# TX.net
KiCad netlist of a schematic drawn in Altium Designer
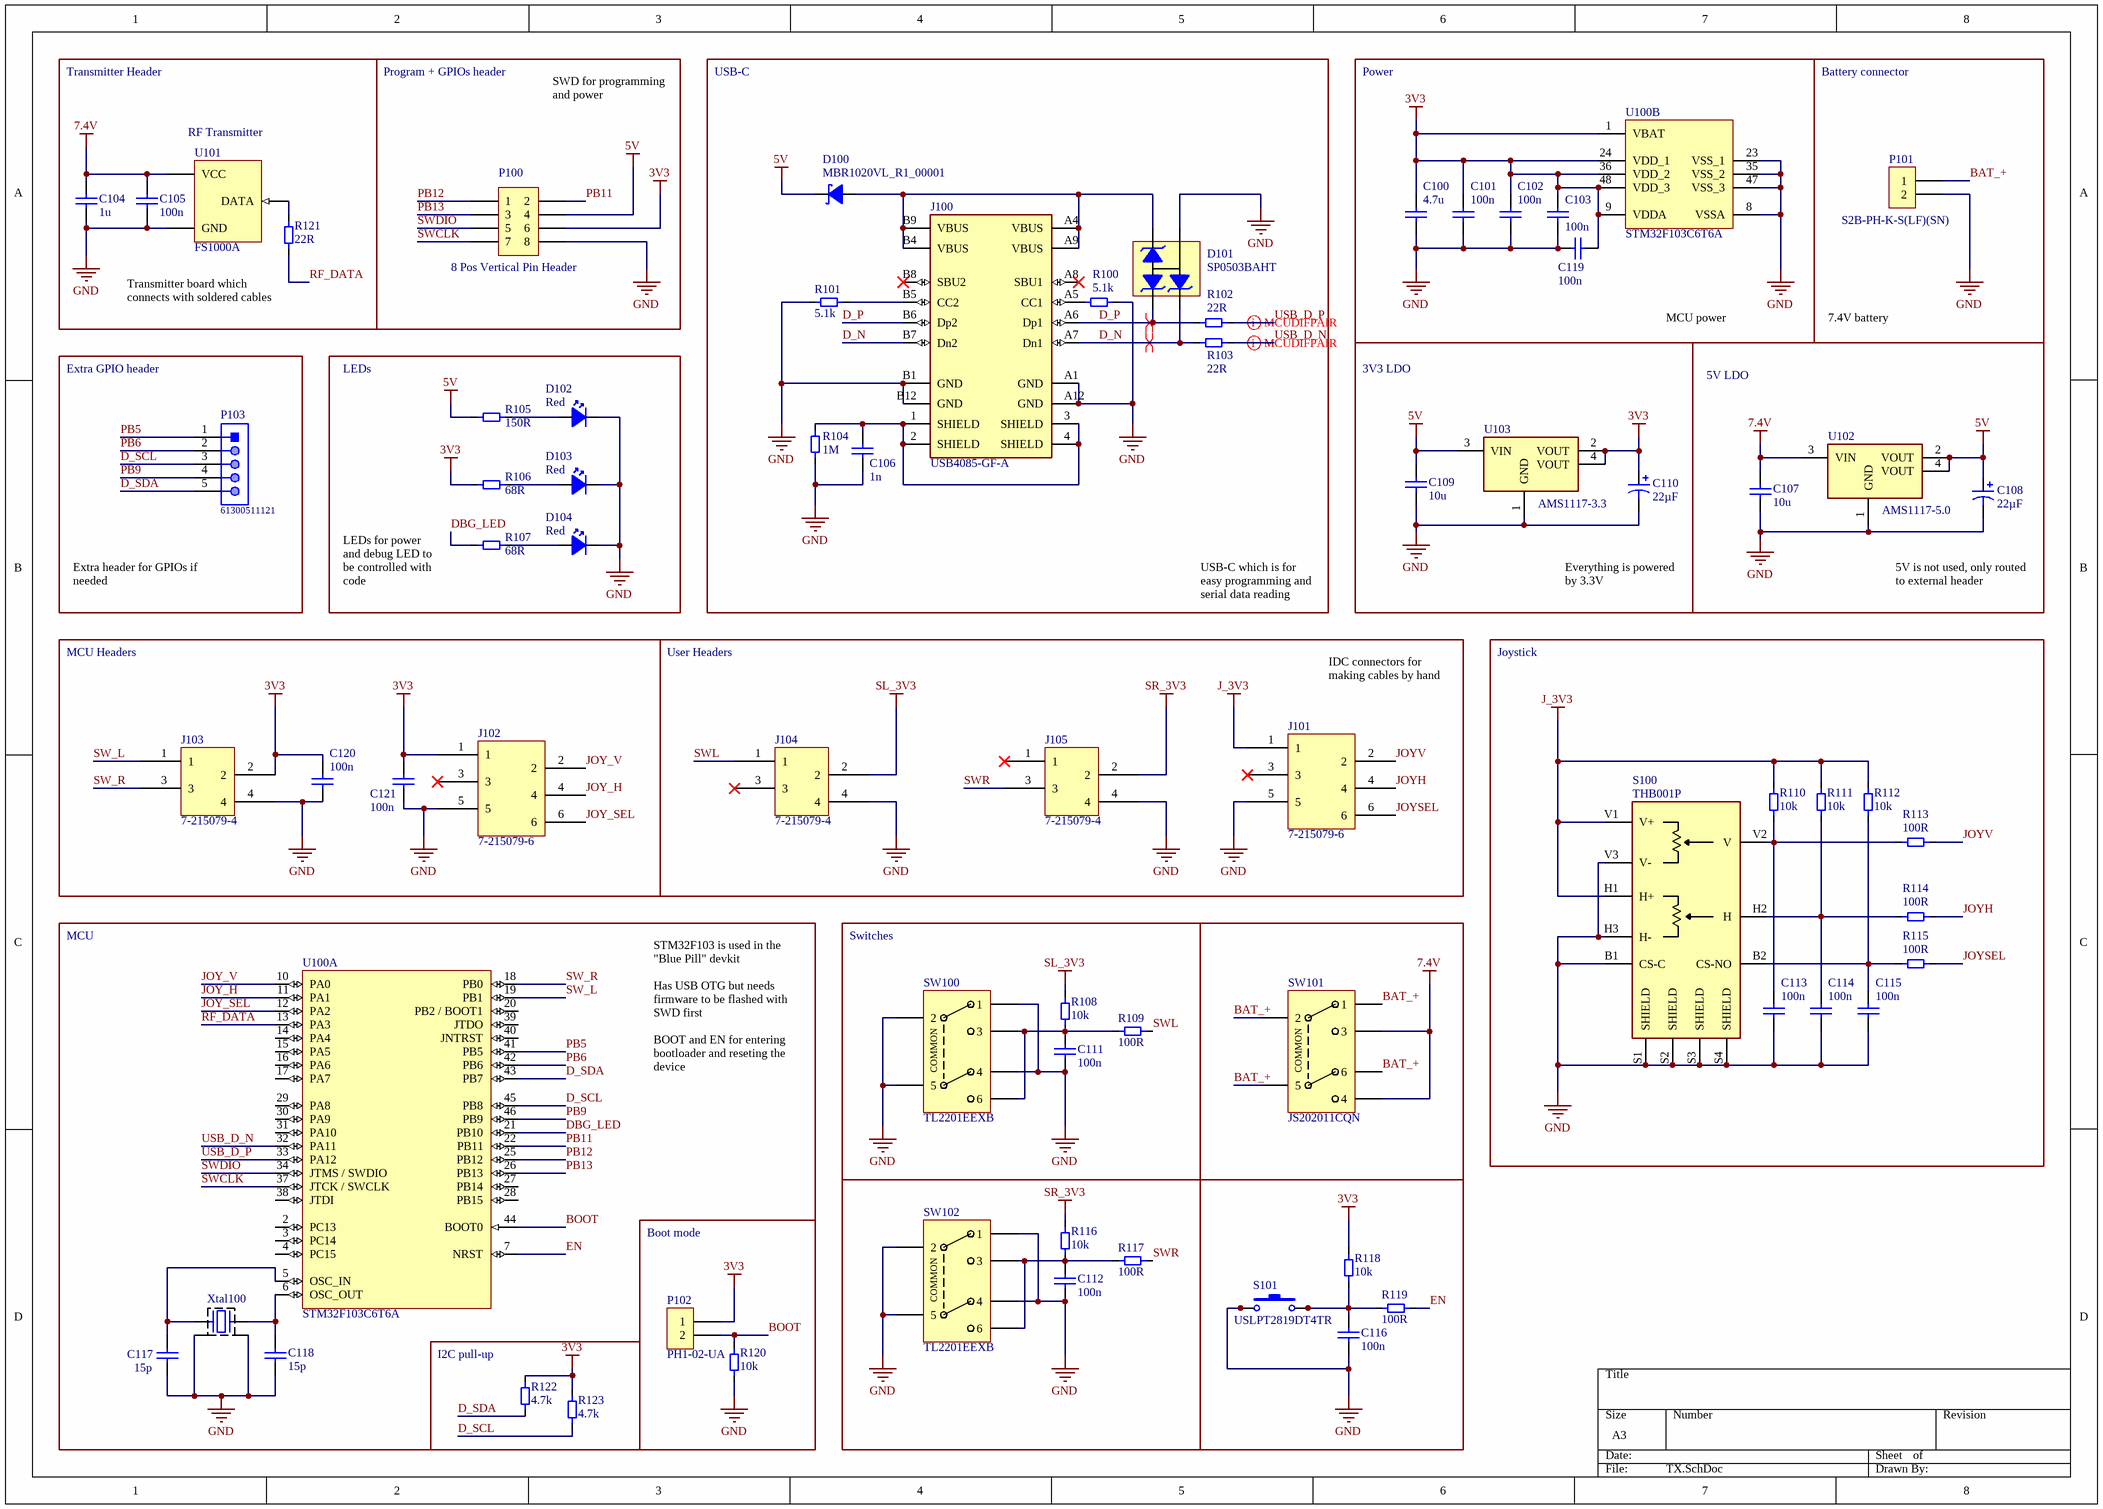
[diagram p0: TX.SchDoc]

(export (version "E")
  (design (tool "Eeschema 10.0.6"))
  (components
    (comp (ref "C100")
      (value "4.7u")
      (footprint "MLCC_0805_M")
      (description "MLCC, 0805, 4.7u, 20%, 50V, X5R")
      (fields (field (name "MANUFACTURER") "Any") (field (name "VOLTAGE") "50V"))
      (libsource (lib "Krakul Vault") (part "CAPACITOR_NONPOL_IEC"))
    )
    (comp (ref "C101")
      (value "100n")
      (footprint "MLCC_0603_M")
      (description "MLCC, 0603, 100n, 10%, 50V, X7R")
      (fields (field (name "VOLTAGE") "50V") (field (name "TOLERANCE") "10%"))
      (libsource (lib "Krakul Vault") (part "CAPACITOR_NONPOL_IEC"))
    )
    (comp (ref "C102")
      (value "100n")
      (footprint "MLCC_0603_M")
      (description "MLCC, 0603, 100n, 10%, 50V, X7R")
      (fields (field (name "VOLTAGE") "50V") (field (name "TOLERANCE") "10%"))
      (libsource (lib "Krakul Vault") (part "CAPACITOR_NONPOL_IEC"))
    )
    (comp (ref "C103")
      (value "100n")
      (footprint "MLCC_0603_M")
      (description "MLCC, 0603, 100n, 10%, 50V, X7R")
      (fields (field (name "VOLTAGE") "50V") (field (name "TOLERANCE") "10%"))
      (libsource (lib "Krakul Vault") (part "CAPACITOR_NONPOL_IEC"))
    )
    (comp (ref "C104")
      (value "1u")
      (footprint "MLCC_0603_M")
      (description "MLCC, 0603, 1u, 10%, 50V, X5R")
      (fields (field (name "MANUFACTURER") "Any") (field (name "VOLTAGE") "50V"))
      (libsource (lib "Krakul Vault") (part "CAPACITOR_NONPOL_IEC"))
    )
    (comp (ref "C105")
      (value "100n")
      (footprint "MLCC_0603_M")
      (description "MLCC, 0603, 100n, 10%, 50V, X7R")
      (fields (field (name "VOLTAGE") "50V") (field (name "TOLERANCE") "10%"))
      (libsource (lib "Krakul Vault") (part "CAPACITOR_NONPOL_IEC"))
    )
    (comp (ref "C106")
      (value "1n")
      (footprint "MLCC_0603_M")
      (description "MLCC, 0603, 1n, 10%, 50V, X7R")
      (fields (field (name "MANUFACTURER") "Any") (field (name "VOLTAGE") "50V"))
      (libsource (lib "Krakul Vault") (part "CAPACITOR_NONPOL_IEC"))
    )
    (comp (ref "C107")
      (value "10u")
      (footprint "MLCC_0805_M")
      (description "MLCC, 0805, 10u, 10%, 50V, X5R")
      (fields (field (name "TOLERANCE") "10%") (field (name "VOLTAGE") "50V"))
      (libsource (lib "Krakul Vault") (part "CAPACITOR_NONPOL_IEC"))
    )
    (comp (ref "C108")
      (value "22µF")
      (footprint "1210_Tantalum")
      (description "Cap Tant Solid 22uF 25V B CASE 20% (3.5 X 2.8 X 1.9mm) SMD 3528-21 0.15 Ohm 105°C T/R")
      (fields (field (name "TOLERANCE") "20%") (field (name "MANUFACTURER") "AVX Corporation"))
      (libsource (lib "Krakul Vault") (part "GENERIC TANT CAP"))
    )
    (comp (ref "C109")
      (value "10u")
      (footprint "MLCC_0805_M")
      (description "MLCC, 0805, 10u, 10%, 50V, X5R")
      (fields (field (name "TOLERANCE") "10%") (field (name "VOLTAGE") "50V"))
      (libsource (lib "Krakul Vault") (part "CAPACITOR_NONPOL_IEC"))
    )
    (comp (ref "C110")
      (value "22µF")
      (footprint "1210_Tantalum")
      (description "Cap Tant Solid 22uF 25V B CASE 20% (3.5 X 2.8 X 1.9mm) SMD 3528-21 0.15 Ohm 105°C T/R")
      (fields (field (name "TOLERANCE") "20%") (field (name "MANUFACTURER") "AVX Corporation"))
      (libsource (lib "Krakul Vault") (part "GENERIC TANT CAP"))
    )
    (comp (ref "C111")
      (value "100n")
      (footprint "MLCC_0603_M")
      (description "MLCC, 0603, 100n, 10%, 50V, X7R")
      (fields (field (name "VOLTAGE") "50V") (field (name "TOLERANCE") "10%"))
      (libsource (lib "Krakul Vault") (part "CAPACITOR_NONPOL_IEC"))
    )
    (comp (ref "C112")
      (value "100n")
      (footprint "MLCC_0603_M")
      (description "MLCC, 0603, 100n, 10%, 50V, X7R")
      (fields (field (name "VOLTAGE") "50V") (field (name "TOLERANCE") "10%"))
      (libsource (lib "Krakul Vault") (part "CAPACITOR_NONPOL_IEC"))
    )
    (comp (ref "C113")
      (value "100n")
      (footprint "MLCC_0603_M")
      (description "MLCC, 0603, 100n, 10%, 50V, X7R")
      (fields (field (name "VOLTAGE") "50V") (field (name "TOLERANCE") "10%"))
      (libsource (lib "Krakul Vault") (part "CAPACITOR_NONPOL_IEC"))
    )
    (comp (ref "C114")
      (value "100n")
      (footprint "MLCC_0603_M")
      (description "MLCC, 0603, 100n, 10%, 50V, X7R")
      (fields (field (name "VOLTAGE") "50V") (field (name "TOLERANCE") "10%"))
      (libsource (lib "Krakul Vault") (part "CAPACITOR_NONPOL_IEC"))
    )
    (comp (ref "C115")
      (value "100n")
      (footprint "MLCC_0603_M")
      (description "MLCC, 0603, 100n, 10%, 50V, X7R")
      (fields (field (name "VOLTAGE") "50V") (field (name "TOLERANCE") "10%"))
      (libsource (lib "Krakul Vault") (part "CAPACITOR_NONPOL_IEC"))
    )
    (comp (ref "C116")
      (value "100n")
      (footprint "MLCC_0603_M")
      (description "MLCC, 0603, 100n, 10%, 50V, X7R")
      (fields (field (name "VOLTAGE") "50V") (field (name "TOLERANCE") "10%"))
      (libsource (lib "Krakul Vault") (part "CAPACITOR_NONPOL_IEC"))
    )
    (comp (ref "C117")
      (value "15p")
      (footprint "MLCC_0402_M")
      (description "MLCC, 0402, 15p, 10%, 25V, C0G/NP0")
      (fields (field (name "MANUFACTURER") "Any") (field (name "TOLERANCE") "10%"))
      (libsource (lib "Krakul Vault") (part "CAPACITOR_NONPOL_IEC"))
    )
    (comp (ref "C118")
      (value "15p")
      (footprint "MLCC_0402_M")
      (description "MLCC, 0402, 15p, 10%, 25V, C0G/NP0")
      (fields (field (name "MANUFACTURER") "Any") (field (name "TOLERANCE") "10%"))
      (libsource (lib "Krakul Vault") (part "CAPACITOR_NONPOL_IEC"))
    )
    (comp (ref "C119")
      (value "100n")
      (footprint "MLCC_0603_M")
      (description "MLCC, 0603, 100n, 10%, 50V, X7R")
      (fields (field (name "VOLTAGE") "50V") (field (name "TOLERANCE") "10%"))
      (libsource (lib "Krakul Vault") (part "CAPACITOR_NONPOL_IEC"))
    )
    (comp (ref "C120")
      (value "100n")
      (footprint "MLCC_0603_M")
      (description "MLCC, 0603, 100n, 10%, 50V, X7R")
      (fields (field (name "VOLTAGE") "50V") (field (name "TOLERANCE") "10%"))
      (libsource (lib "Krakul Vault") (part "CAPACITOR_NONPOL_IEC"))
    )
    (comp (ref "C121")
      (value "100n")
      (footprint "MLCC_0603_M")
      (description "MLCC, 0603, 100n, 10%, 50V, X7R")
      (fields (field (name "VOLTAGE") "50V") (field (name "TOLERANCE") "10%"))
      (libsource (lib "Krakul Vault") (part "CAPACITOR_NONPOL_IEC"))
    )
    (comp (ref "D100")
      (value "MBR1020VL_R1_00001")
      (footprint "FP-MBR1020VL_R1_00001-MFG")
      (description "Rectifier Diode, Schottky, 1 Phase, 1 Element, 1A, 20V V(RRM), Silicon")
      (fields (field (name "MANUFACTURER") "Panjit"))
      (libsource (lib "Krakul Vault") (part "Schottky generic 2 pins"))
    )
    (comp (ref "D101")
      (value "SP0503BAHT")
      (footprint "LFUS-SOT143-4_V")
      (description "SP050xBA Series 8.5 V 30 pF Triple Uni-Directional TVS Avalanche Diode-SOT143-4")
      (fields (field (name "MANUFACTURER") "Littelfuse Inc."))
      (libsource (lib "Krakul Vault") (part "SOT-143"))
    )
    (comp (ref "D102")
      (value "Red")
      (footprint "0603 RED LED")
      (description "Generic red 0603 LED")
      (fields (field (name "PART NUMBER") "Any Red 0603 LED") (field (name "MANUFACTURER") "Any"))
      (libsource (lib "Krakul Vault") (part "LED generic"))
    )
    (comp (ref "D103")
      (value "Red")
      (footprint "0603 RED LED")
      (description "Generic red 0603 LED")
      (fields (field (name "PART NUMBER") "Any Red 0603 LED") (field (name "MANUFACTURER") "Any"))
      (libsource (lib "Krakul Vault") (part "LED generic"))
    )
    (comp (ref "D104")
      (value "Red")
      (footprint "0603 RED LED")
      (description "Generic red 0603 LED")
      (fields (field (name "PART NUMBER") "Any Red 0603 LED") (field (name "MANUFACTURER") "Any"))
      (libsource (lib "Krakul Vault") (part "LED generic"))
    )
    (comp (ref "J100")
      (value "USB4085-GF-A")
      (footprint "FP-USB4085-GF-A-MFG")
      (description "USB Connector, 16 Contact(s), Female, Right Angle, Solder Terminal, Locking, Receptacle")
      (fields (field (name "MANUFACTURER") "GCT") (field (name "PART NUMBER") "USB4800-03-A"))
      (libsource (lib "Krakul Vault") (part "USB4085-GF-A"))
    )
    (comp (ref "J101")
      (value "7-215079-6")
      (footprint "7-215079-6-Footprint-1")
      (description "Conn FFC Connector F 6 POS 1.27mm Solder ST Thru-Hole Automotive Box/Carton")
      (fields (field (name "MANUFACTURER") "TE Connectivity"))
      (libsource (lib "Krakul Vault") (part "7-215079-6"))
    )
    (comp (ref "J102")
      (value "7-215079-6")
      (footprint "7-215079-6-Footprint-1")
      (description "Conn FFC Connector F 6 POS 1.27mm Solder ST Thru-Hole Automotive Box/Carton")
      (fields (field (name "MANUFACTURER") "TE Connectivity"))
      (libsource (lib "Krakul Vault") (part "7-215079-6"))
    )
    (comp (ref "J103")
      (value "7-215079-4")
      (footprint "7-215079-4")
      (description "Conn FFC Connector F 4 POS 1.27mm Solder ST Thru-Hole Box/Carton")
      (fields (field (name "MANUFACTURER") "TE connectivity") (field (name "PART NUMBER") "7-215079-6"))
      (libsource (lib "Krakul Vault") (part "7-215079-4"))
    )
    (comp (ref "J104")
      (value "7-215079-4")
      (footprint "7-215079-4")
      (description "Conn FFC Connector F 4 POS 1.27mm Solder ST Thru-Hole Box/Carton")
      (fields (field (name "MANUFACTURER") "TE connectivity") (field (name "PART NUMBER") "7-215079-6"))
      (libsource (lib "Krakul Vault") (part "7-215079-4"))
    )
    (comp (ref "J105")
      (value "7-215079-4")
      (footprint "7-215079-4")
      (description "Conn FFC Connector F 4 POS 1.27mm Solder ST Thru-Hole Box/Carton")
      (fields (field (name "MANUFACTURER") "TE connectivity") (field (name "PART NUMBER") "7-215079-6"))
      (libsource (lib "Krakul Vault") (part "7-215079-4"))
    )
    (comp (ref "P100")
      (value "8 Pos Vertical Pin Header")
      (footprint "8 POS Vertical Pin Header")
      (description "Connector Header Through Hole 8 position 0.100\" (2.54mm)")
      (fields (field (name "MANUFACTURER") "Amphenol ICC (FCI)") (field (name "PART NUMBER") "67997-208HLF"))
      (libsource (lib "Krakul Vault") (part "8POS GENERIC 2-LINE"))
    )
    (comp (ref "P101")
      (value "S2B-PH-K-S(LF)(SN)")
      (footprint "B5B-PH-K-S(LF)(SN)")
      (description "Conn Shrouded Header (4 Sides) HDR 2 POS 2mm Solder RA Thru-Hole Box")
      (fields (field (name "MANUFACTURER") "JST Sales America Inc."))
      (libsource (lib "Krakul Vault") (part "2POS GENERIC"))
    )
    (comp (ref "P102")
      (value "PH1-02-UA")
      (footprint "2Pos Pin Header Vertical")
      (description "Conn Unshrouded Header HDR 2 POS 2.54mm Solder ST Top Entry Thru-Hole Bag")
      (fields (field (name "PART NUMBER") "PH1-04-UA") (field (name "MANUFACTURER") "Adam Tech"))
      (libsource (lib "Krakul Vault") (part "2POS GENERIC"))
    )
    (comp (ref "P103")
      (value "61300511121")
      (footprint "61300511121")
      (description "Conn Unshrouded Header HDR 5 POS 2.54mm Solder ST Top Entry Thru-Hole Bag")
      (fields (field (name "MANUFACTURER") "Wurth"))
      (libsource (lib "Krakul Vault") (part "WE-CN-1P-M-R5"))
    )
    (comp (ref "R100")
      (value "5.1k")
      (footprint "Resistor_0603_M")
      (description "Resistor, 0603, 5.1k, 1%, 1/10W")
      (fields (field (name "POWER") "100mW") (field (name "MANUFACTURER") "Any"))
      (libsource (lib "Krakul Vault") (part "RESISTOR_GENERIC_IEC"))
    )
    (comp (ref "R101")
      (value "5.1k")
      (footprint "Resistor_0603_M")
      (description "Resistor, 0603, 5.1k, 1%, 1/10W")
      (fields (field (name "POWER") "100mW") (field (name "MANUFACTURER") "Any"))
      (libsource (lib "Krakul Vault") (part "RESISTOR_GENERIC_IEC"))
    )
    (comp (ref "R102")
      (value "22R")
      (footprint "Resistor_0603_M")
      (description "Resistor, 0603, 22R, 1%, 1/10W")
      (fields (field (name "TOLERANCE") "1%") (field (name "MANUFACTURER") "Any"))
      (libsource (lib "Krakul Vault") (part "RESISTOR_GENERIC_IEC"))
    )
    (comp (ref "R103")
      (value "22R")
      (footprint "Resistor_0603_M")
      (description "Resistor, 0603, 22R, 1%, 1/10W")
      (fields (field (name "TOLERANCE") "1%") (field (name "MANUFACTURER") "Any"))
      (libsource (lib "Krakul Vault") (part "RESISTOR_GENERIC_IEC"))
    )
    (comp (ref "R104")
      (value "1M")
      (footprint "Resistor_1206_M")
      (description "Resistor, 1206, 1M, 1%, 1/4W")
      (fields (field (name "MANUFACTURER") "Any"))
      (libsource (lib "Krakul Vault") (part "RESISTOR_GENERIC_IEC"))
    )
    (comp (ref "R105")
      (value "150R")
      (footprint "Resistor_0603_M")
      (description "Resistor, 0603, 200R, 1%, 1/10W")
      (fields (field (name "TOLERANCE") "1%") (field (name "POWER") "100mW"))
      (libsource (lib "Krakul Vault") (part "RESISTOR_GENERIC_IEC"))
    )
    (comp (ref "R106")
      (value "68R")
      (footprint "Resistor_0603_M")
      (description "Resistor, 0603, 200R, 1%, 1/10W")
      (fields (field (name "TOLERANCE") "1%") (field (name "POWER") "100mW"))
      (libsource (lib "Krakul Vault") (part "RESISTOR_GENERIC_IEC"))
    )
    (comp (ref "R107")
      (value "68R")
      (footprint "Resistor_0603_M")
      (description "Resistor, 0603, 200R, 1%, 1/10W")
      (fields (field (name "TOLERANCE") "1%") (field (name "POWER") "100mW"))
      (libsource (lib "Krakul Vault") (part "RESISTOR_GENERIC_IEC"))
    )
    (comp (ref "R108")
      (value "10k")
      (footprint "Resistor_0603_M")
      (description "Resistor, 0603, 10k, 1%, 1/10W")
      (fields (field (name "MANUFACTURER") "Any") (field (name "TOLERANCE") "1%"))
      (libsource (lib "Krakul Vault") (part "RESISTOR_GENERIC_IEC"))
    )
    (comp (ref "R109")
      (value "100R")
      (footprint "Resistor_0603_M")
      (description "Resistor, 0603, 100R, 1%, 1/10W")
      (fields (field (name "POWER") "100mW") (field (name "MANUFACTURER") "Any"))
      (libsource (lib "Krakul Vault") (part "RESISTOR_GENERIC_IEC"))
    )
    (comp (ref "R110")
      (value "10k")
      (footprint "Resistor_0603_M")
      (description "Resistor, 0603, 10k, 1%, 1/10W")
      (fields (field (name "MANUFACTURER") "Any") (field (name "TOLERANCE") "1%"))
      (libsource (lib "Krakul Vault") (part "RESISTOR_GENERIC_IEC"))
    )
    (comp (ref "R111")
      (value "10k")
      (footprint "Resistor_0603_M")
      (description "Resistor, 0603, 10k, 1%, 1/10W")
      (fields (field (name "MANUFACTURER") "Any") (field (name "TOLERANCE") "1%"))
      (libsource (lib "Krakul Vault") (part "RESISTOR_GENERIC_IEC"))
    )
    (comp (ref "R112")
      (value "10k")
      (footprint "Resistor_0603_M")
      (description "Resistor, 0603, 10k, 1%, 1/10W")
      (fields (field (name "MANUFACTURER") "Any") (field (name "TOLERANCE") "1%"))
      (libsource (lib "Krakul Vault") (part "RESISTOR_GENERIC_IEC"))
    )
    (comp (ref "R113")
      (value "100R")
      (footprint "Resistor_0603_M")
      (description "Resistor, 0603, 100R, 1%, 1/10W")
      (fields (field (name "POWER") "100mW") (field (name "MANUFACTURER") "Any"))
      (libsource (lib "Krakul Vault") (part "RESISTOR_GENERIC_IEC"))
    )
    (comp (ref "R114")
      (value "100R")
      (footprint "Resistor_0603_M")
      (description "Resistor, 0603, 100R, 1%, 1/10W")
      (fields (field (name "POWER") "100mW") (field (name "MANUFACTURER") "Any"))
      (libsource (lib "Krakul Vault") (part "RESISTOR_GENERIC_IEC"))
    )
    (comp (ref "R115")
      (value "100R")
      (footprint "Resistor_0603_M")
      (description "Resistor, 0603, 100R, 1%, 1/10W")
      (fields (field (name "POWER") "100mW") (field (name "MANUFACTURER") "Any"))
      (libsource (lib "Krakul Vault") (part "RESISTOR_GENERIC_IEC"))
    )
    (comp (ref "R116")
      (value "10k")
      (footprint "Resistor_0603_M")
      (description "Resistor, 0603, 10k, 1%, 1/10W")
      (fields (field (name "MANUFACTURER") "Any") (field (name "TOLERANCE") "1%"))
      (libsource (lib "Krakul Vault") (part "RESISTOR_GENERIC_IEC"))
    )
    (comp (ref "R117")
      (value "100R")
      (footprint "Resistor_0603_M")
      (description "Resistor, 0603, 100R, 1%, 1/10W")
      (fields (field (name "POWER") "100mW") (field (name "MANUFACTURER") "Any"))
      (libsource (lib "Krakul Vault") (part "RESISTOR_GENERIC_IEC"))
    )
    (comp (ref "R118")
      (value "10k")
      (footprint "Resistor_0603_M")
      (description "Resistor, 0603, 10k, 1%, 1/10W")
      (fields (field (name "MANUFACTURER") "Any") (field (name "TOLERANCE") "1%"))
      (libsource (lib "Krakul Vault") (part "RESISTOR_GENERIC_IEC"))
    )
    (comp (ref "R119")
      (value "100R")
      (footprint "Resistor_0603_M")
      (description "Resistor, 0603, 100R, 1%, 1/10W")
      (fields (field (name "POWER") "100mW") (field (name "MANUFACTURER") "Any"))
      (libsource (lib "Krakul Vault") (part "RESISTOR_GENERIC_IEC"))
    )
    (comp (ref "R120")
      (value "10k")
      (footprint "Resistor_0603_M")
      (description "Resistor, 0603, 10k, ≤5%, ≥1/16W")
      (fields (field (name "MANUFACTURER") "Any"))
      (libsource (lib "Krakul Vault") (part "RESISTOR_GENERIC_IEC"))
    )
    (comp (ref "R121")
      (value "22R")
      (footprint "Resistor_0603_M")
      (description "Resistor, 0603, 22R, 1%, 1/10W")
      (fields (field (name "TOLERANCE") "1%") (field (name "MANUFACTURER") "Any"))
      (libsource (lib "Krakul Vault") (part "RESISTOR_GENERIC_IEC"))
    )
    (comp (ref "R122")
      (value "4.7k")
      (footprint "Resistor_0603_M")
      (description "Resistor, 0603, 4.7k, 1%, 1/10W")
      (fields (field (name "MANUFACTURER") "Any") (field (name "POWER") "100mW"))
      (libsource (lib "Krakul Vault") (part "RESISTOR_GENERIC_IEC"))
    )
    (comp (ref "R123")
      (value "4.7k")
      (footprint "Resistor_0603_M")
      (description "Resistor, 0603, 4.7k, 1%, 1/10W")
      (fields (field (name "MANUFACTURER") "Any") (field (name "POWER") "100mW"))
      (libsource (lib "Krakul Vault") (part "RESISTOR_GENERIC_IEC"))
    )
    (comp (ref "S100")
      (value "THB001P")
      (footprint "THB001P")
      (description "Multi-Directional Thumbstick, 2 Axis, Center Momentary Switch, 12VDC, THB Series")
      (fields (field (name "MANUFACTURER") "Littelfuse"))
      (libsource (lib "Krakul Vault") (part "THB001P"))
    )
    (comp (ref "S101")
      (value "USLPT2819DT4TR")
      (footprint "USLPT2819DT4TR-Footprint-1")
      (description "Keypad Switch, SPST, 0.05A, 1.96N, Solder Terminal, Panel Mount")
      (fields (field (name "MANUFACTURER") "TE Connectivity ALCOSWITCH Switches"))
      (libsource (lib "Krakul Vault") (part "Copy of Switch 4-pin"))
    )
    (comp (ref "SW100")
      (value "TL2201EEXB")
      (footprint "TL2201EEXB-Footprint-1")
      (description "Pushbutton Switch, DPDT, ON-ON, 100 mA, 30V DC, PC Pin, TL2201 Series")
      (fields (field (name "MANUFACTURER") "E-Switch"))
      (libsource (lib "Krakul Vault") (part "TL2201EEXB-Symbol-1"))
    )
    (comp (ref "SW101")
      (value "JS202011CQN")
      (footprint "FP-JS202011CQN-MFG")
      (description "Slide Switch, 1 Positions, Dpdt, Latched, 0.3A, 6Vdc, 6 Pcb Hole Cnt, Solder Terminal, Through")
      (fields (field (name "MANUFACTURER") "C&K"))
      (libsource (lib "Krakul Vault") (part "JS202011CQN-Symbol-1"))
    )
    (comp (ref "SW102")
      (value "TL2201EEXB")
      (footprint "TL2201EEXB-Footprint-1")
      (description "Pushbutton Switch, DPDT, ON-ON, 100 mA, 30V DC, PC Pin, TL2201 Series")
      (fields (field (name "MANUFACTURER") "E-Switch"))
      (libsource (lib "Krakul Vault") (part "TL2201EEXB-Symbol-1"))
    )
    (comp (ref "U100")
      (value "STM32F103C6T6A")
      (footprint "STM-LQFP48_M")
      (description "MCU 32-bit STM32F ARM Cortex M3 RISC 32KB Flash 2.5V/3.3V 48-Pin LQFP Tray")
      (fields (field (name "MANUFACTURER") "STMicroelectronics") (field (name "PART NUMBER") "STM32F103C8T6"))
      (libsource (lib "Krakul Vault") (part "MC-ARM-STM32F103X4_6-SQ48"))
    )
    (comp (ref "U101")
      (value "FS1000A")
      (footprint "2.54mm 3-pin horizontal")
      (description "FS1000A 433MHZ RF transmitter & XY-MK-5V Receiver Module")
      (libsource (lib "Krakul Vault") (part "FS1000A"))
    )
    (comp (ref "U102")
      (value "AMS1117-5.0")
      (footprint "SOT230P700X180-4N")
      (description "LDO Regulator Pos 5V 1A 4-Pin(3+Tab) SOT-223 / 1A LOW DROPOUT VOLTAGE REGULATOR")
      (fields (field (name "MANUFACTURER") "EVVO"))
      (libsource (lib "Krakul Vault") (part "AMS1117-3.3"))
    )
    (comp (ref "U103")
      (value "AMS1117-3.3")
      (footprint "SOT-223 based on ZVP2110GTA")
      (fields (field (name "MANUFACTURER") "Shenzhen Slkormicro Semicon Co., Ltd."))
      (libsource (lib "Krakul Vault") (part "AMS1117-3.3"))
    )
    (comp (ref "Xtal100")
      (value "ABM11-16.000MHZ-12-N1G-T")
      (footprint "FP-ABM11-MFG")
      (description "Crystal 16MHz ±10ppm (Tol) ±15ppm (Stability) 12pF FUND 150Ohm 4-Pin Ultra Mini-CSMD T/R")
      (fields (field (name "MANUFACTURER") "Abracon LLC") (field (name "TOLERANCE") "0.001%"))
      (libsource (lib "Krakul Vault") (part "Crystal 4 pins"))
    )
  )
  (nets
    (net (code "1") (name "/BAT_+") (class "Default")
      (node (ref "P101") (pin "1") (pinfunction "1_1") (pintype "passive"))
      (node (ref "SW101") (pin "1") (pinfunction "1_1") (pintype "passive"))
      (node (ref "SW101") (pin "2") (pinfunction "2_2") (pintype "passive"))
      (node (ref "SW101") (pin "5") (pinfunction "5_5") (pintype "passive"))
      (node (ref "SW101") (pin "6") (pinfunction "6_6") (pintype "passive"))
    )
    (net (code "2") (name "/BOOT") (class "Default")
      (node (ref "P102") (pin "2") (pinfunction "2_2") (pintype "passive"))
      (node (ref "R120") (pin "2") (pinfunction "2_2") (pintype "passive"))
      (node (ref "U100") (pin "44") (pinfunction "BOOT0_44") (pintype "input"))
    )
    (net (code "3") (name "/DBG_LED") (class "Default")
      (node (ref "R107") (pin "1") (pinfunction "1_1") (pintype "passive"))
      (node (ref "U100") (pin "21") (pinfunction "PB10_21") (pintype "bidirectional"))
    )
    (net (code "4") (name "/D_N") (class "Default")
      (node (ref "D101") (pin "4") (pinfunction "C_4") (pintype "passive"))
      (node (ref "J100") (pin "A7") (pinfunction "Dn1_A7") (pintype "bidirectional"))
      (node (ref "J100") (pin "B7") (pinfunction "Dn2_B7") (pintype "bidirectional"))
      (node (ref "R103") (pin "1") (pinfunction "1_1") (pintype "passive"))
    )
    (net (code "5") (name "/D_P") (class "Default")
      (node (ref "D101") (pin "3") (pinfunction "C_3") (pintype "passive"))
      (node (ref "J100") (pin "A6") (pinfunction "Dp1_A6") (pintype "bidirectional"))
      (node (ref "J100") (pin "B6") (pinfunction "Dp2_B6") (pintype "bidirectional"))
      (node (ref "R102") (pin "1") (pinfunction "1_1") (pintype "passive"))
    )
    (net (code "6") (name "/D_SCL") (class "Default")
      (node (ref "P103") (pin "3") (pinfunction "3_3") (pintype "passive"))
      (node (ref "R123") (pin "1") (pinfunction "1_1") (pintype "passive"))
      (node (ref "U100") (pin "45") (pinfunction "PB8_45") (pintype "bidirectional"))
    )
    (net (code "7") (name "/D_SDA") (class "Default")
      (node (ref "P103") (pin "5") (pinfunction "5_5") (pintype "passive"))
      (node (ref "R122") (pin "1") (pinfunction "1_1") (pintype "passive"))
      (node (ref "U100") (pin "43") (pinfunction "PB7_43") (pintype "bidirectional"))
    )
    (net (code "8") (name "/EN") (class "Default")
      (node (ref "R119") (pin "2") (pinfunction "2_2") (pintype "passive"))
      (node (ref "U100") (pin "7") (pinfunction "NRST_7") (pintype "bidirectional"))
    )
    (net (code "9") (name "/JOYH") (class "Default")
      (node (ref "J101") (pin "4") (pinfunction "4_4") (pintype "passive"))
      (node (ref "R114") (pin "2") (pinfunction "2_2") (pintype "passive"))
    )
    (net (code "10") (name "/JOYSEL") (class "Default")
      (node (ref "J101") (pin "6") (pinfunction "6_6") (pintype "passive"))
      (node (ref "R115") (pin "2") (pinfunction "2_2") (pintype "passive"))
    )
    (net (code "11") (name "/JOYV") (class "Default")
      (node (ref "J101") (pin "2") (pinfunction "2_2") (pintype "passive"))
      (node (ref "R113") (pin "2") (pinfunction "2_2") (pintype "passive"))
    )
    (net (code "12") (name "/JOY_H") (class "Default")
      (node (ref "J102") (pin "4") (pinfunction "4_4") (pintype "passive"))
      (node (ref "U100") (pin "11") (pinfunction "PA1_11") (pintype "bidirectional"))
    )
    (net (code "13") (name "/JOY_SEL") (class "Default")
      (node (ref "J102") (pin "6") (pinfunction "6_6") (pintype "passive"))
      (node (ref "U100") (pin "12") (pinfunction "PA2_12") (pintype "bidirectional"))
    )
    (net (code "14") (name "/JOY_V") (class "Default")
      (node (ref "J102") (pin "2") (pinfunction "2_2") (pintype "passive"))
      (node (ref "U100") (pin "10") (pinfunction "PA0_10") (pintype "bidirectional"))
    )
    (net (code "15") (name "/PB5") (class "Default")
      (node (ref "P103") (pin "1") (pinfunction "1_1") (pintype "passive"))
      (node (ref "U100") (pin "41") (pinfunction "PB5_41") (pintype "bidirectional"))
    )
    (net (code "16") (name "/PB6") (class "Default")
      (node (ref "P103") (pin "2") (pinfunction "2_2") (pintype "passive"))
      (node (ref "U100") (pin "42") (pinfunction "PB6_42") (pintype "bidirectional"))
    )
    (net (code "17") (name "/PB9") (class "Default")
      (node (ref "P103") (pin "4") (pinfunction "4_4") (pintype "passive"))
      (node (ref "U100") (pin "46") (pinfunction "PB9_46") (pintype "bidirectional"))
    )
    (net (code "18") (name "/PB11") (class "Default")
      (node (ref "P100") (pin "2") (pinfunction "2_2") (pintype "passive"))
      (node (ref "U100") (pin "22") (pinfunction "PB11_22") (pintype "bidirectional"))
    )
    (net (code "19") (name "/PB12") (class "Default")
      (node (ref "P100") (pin "1") (pinfunction "1_1") (pintype "passive"))
      (node (ref "U100") (pin "25") (pinfunction "PB12_25") (pintype "bidirectional"))
    )
    (net (code "20") (name "/PB13") (class "Default")
      (node (ref "P100") (pin "3") (pinfunction "3_3") (pintype "passive"))
      (node (ref "U100") (pin "26") (pinfunction "PB13_26") (pintype "bidirectional"))
    )
    (net (code "21") (name "/RF_DATA") (class "Default")
      (node (ref "R121") (pin "2") (pinfunction "2_2") (pintype "passive"))
      (node (ref "U100") (pin "13") (pinfunction "PA3_13") (pintype "bidirectional"))
    )
    (net (code "22") (name "/SWCLK") (class "Default")
      (node (ref "P100") (pin "7") (pinfunction "7_7") (pintype "passive"))
      (node (ref "U100") (pin "37") (pinfunction "JTCK_/_SWCLK_37") (pintype "bidirectional"))
    )
    (net (code "23") (name "/SWDIO") (class "Default")
      (node (ref "P100") (pin "5") (pinfunction "5_5") (pintype "passive"))
      (node (ref "U100") (pin "34") (pinfunction "JTMS_/_SWDIO_34") (pintype "bidirectional"))
    )
    (net (code "24") (name "/SWL") (class "Default")
      (node (ref "J104") (pin "1") (pinfunction "1_1") (pintype "passive"))
      (node (ref "R109") (pin "2") (pinfunction "2_2") (pintype "passive"))
    )
    (net (code "25") (name "/SWR") (class "Default")
      (node (ref "J105") (pin "3") (pinfunction "3_3") (pintype "passive"))
      (node (ref "R117") (pin "2") (pinfunction "2_2") (pintype "passive"))
    )
    (net (code "26") (name "/SW_L") (class "Default")
      (node (ref "J103") (pin "1") (pinfunction "1_1") (pintype "passive"))
      (node (ref "U100") (pin "19") (pinfunction "PB1_19") (pintype "bidirectional"))
    )
    (net (code "27") (name "/SW_R") (class "Default")
      (node (ref "J103") (pin "3") (pinfunction "3_3") (pintype "passive"))
      (node (ref "U100") (pin "18") (pinfunction "PB0_18") (pintype "bidirectional"))
    )
    (net (code "28") (name "/USB_D_N") (class "Default")
      (node (ref "R103") (pin "2") (pinfunction "2_2") (pintype "passive"))
      (node (ref "U100") (pin "32") (pinfunction "PA11_32") (pintype "bidirectional"))
    )
    (net (code "29") (name "/USB_D_P") (class "Default")
      (node (ref "R102") (pin "2") (pinfunction "2_2") (pintype "passive"))
      (node (ref "U100") (pin "33") (pinfunction "PA12_33") (pintype "bidirectional"))
    )
    (net (code "30") (name "3V3") (class "Default")
      (node (ref "C100") (pin "2") (pinfunction "2_2") (pintype "passive"))
      (node (ref "C101") (pin "1") (pinfunction "1_1") (pintype "passive"))
      (node (ref "C102") (pin "1") (pinfunction "1_1") (pintype "passive"))
      (node (ref "C103") (pin "1") (pinfunction "1_1") (pintype "passive"))
      (node (ref "C110") (pin "1") (pinfunction "1_1") (pintype "passive"))
      (node (ref "C119") (pin "2") (pinfunction "2_2") (pintype "passive"))
      (node (ref "C120") (pin "2") (pinfunction "2_2") (pintype "passive"))
      (node (ref "C121") (pin "2") (pinfunction "2_2") (pintype "passive"))
      (node (ref "J102") (pin "1") (pinfunction "1_1") (pintype "passive"))
      (node (ref "J103") (pin "2") (pinfunction "2_2") (pintype "passive"))
      (node (ref "P100") (pin "6") (pinfunction "6_6") (pintype "passive"))
      (node (ref "P102") (pin "1") (pinfunction "1_1") (pintype "passive"))
      (node (ref "R106") (pin "1") (pinfunction "1_1") (pintype "passive"))
      (node (ref "R118") (pin "2") (pinfunction "2_2") (pintype "passive"))
      (node (ref "R122") (pin "2") (pinfunction "2_2") (pintype "passive"))
      (node (ref "R123") (pin "2") (pinfunction "2_2") (pintype "passive"))
      (node (ref "U100") (pin "1") (pinfunction "VBAT_1") (pintype "power_in"))
      (node (ref "U100") (pin "24") (pinfunction "VDD_1_24") (pintype "power_in"))
      (node (ref "U100") (pin "36") (pinfunction "VDD_2_36") (pintype "power_in"))
      (node (ref "U100") (pin "48") (pinfunction "VDD_3_48") (pintype "power_in"))
      (node (ref "U100") (pin "9") (pinfunction "VDDA_9") (pintype "power_in"))
      (node (ref "U103") (pin "2") (pinfunction "VOUT_2") (pintype "passive"))
      (node (ref "U103") (pin "4") (pinfunction "VOUT_4") (pintype "passive"))
    )
    (net (code "31") (name "5V") (class "Default")
      (node (ref "C108") (pin "1") (pinfunction "1_1") (pintype "passive"))
      (node (ref "C109") (pin "2") (pinfunction "2_2") (pintype "passive"))
      (node (ref "D100") (pin "1") (pinfunction "C_1") (pintype "passive"))
      (node (ref "P100") (pin "4") (pinfunction "4_4") (pintype "passive"))
      (node (ref "R105") (pin "1") (pinfunction "1_1") (pintype "passive"))
      (node (ref "U102") (pin "2") (pinfunction "VOUT_2") (pintype "passive"))
      (node (ref "U102") (pin "4") (pinfunction "VOUT_4") (pintype "passive"))
      (node (ref "U103") (pin "3") (pinfunction "VIN_3") (pintype "power_in"))
    )
    (net (code "32") (name "7.4V") (class "Default")
      (node (ref "C104") (pin "2") (pinfunction "2_2") (pintype "passive"))
      (node (ref "C105") (pin "2") (pinfunction "2_2") (pintype "passive"))
      (node (ref "C107") (pin "2") (pinfunction "2_2") (pintype "passive"))
      (node (ref "SW101") (pin "3") (pinfunction "3_3") (pintype "passive"))
      (node (ref "SW101") (pin "4") (pinfunction "4_4") (pintype "passive"))
      (node (ref "U101") (pin "2") (pinfunction "VCC_2") (pintype "power_in"))
      (node (ref "U102") (pin "3") (pinfunction "VIN_3") (pintype "power_in"))
    )
    (net (code "33") (name "GND") (class "Default")
      (node (ref "C100") (pin "1") (pinfunction "1_1") (pintype "passive"))
      (node (ref "C101") (pin "2") (pinfunction "2_2") (pintype "passive"))
      (node (ref "C102") (pin "2") (pinfunction "2_2") (pintype "passive"))
      (node (ref "C103") (pin "2") (pinfunction "2_2") (pintype "passive"))
      (node (ref "C104") (pin "1") (pinfunction "1_1") (pintype "passive"))
      (node (ref "C105") (pin "1") (pinfunction "1_1") (pintype "passive"))
      (node (ref "C106") (pin "1") (pinfunction "1_1") (pintype "passive"))
      (node (ref "C107") (pin "1") (pinfunction "1_1") (pintype "passive"))
      (node (ref "C108") (pin "2") (pinfunction "2_2") (pintype "passive"))
      (node (ref "C109") (pin "1") (pinfunction "1_1") (pintype "passive"))
      (node (ref "C110") (pin "2") (pinfunction "2_2") (pintype "passive"))
      (node (ref "C111") (pin "1") (pinfunction "1_1") (pintype "passive"))
      (node (ref "C112") (pin "1") (pinfunction "1_1") (pintype "passive"))
      (node (ref "C113") (pin "1") (pinfunction "1_1") (pintype "passive"))
      (node (ref "C114") (pin "1") (pinfunction "1_1") (pintype "passive"))
      (node (ref "C115") (pin "1") (pinfunction "1_1") (pintype "passive"))
      (node (ref "C116") (pin "1") (pinfunction "1_1") (pintype "passive"))
      (node (ref "C117") (pin "1") (pinfunction "1_1") (pintype "passive"))
      (node (ref "C118") (pin "1") (pinfunction "1_1") (pintype "passive"))
      (node (ref "C119") (pin "1") (pinfunction "1_1") (pintype "passive"))
      (node (ref "C120") (pin "1") (pinfunction "1_1") (pintype "passive"))
      (node (ref "C121") (pin "1") (pinfunction "1_1") (pintype "passive"))
      (node (ref "D101") (pin "1") (pinfunction "A_1") (pintype "passive"))
      (node (ref "D102") (pin "1") (pinfunction "C_1") (pintype "passive"))
      (node (ref "D103") (pin "1") (pinfunction "C_1") (pintype "passive"))
      (node (ref "D104") (pin "1") (pinfunction "C_1") (pintype "passive"))
      (node (ref "J100") (pin "A1") (pinfunction "GND_A1") (pintype "power_in"))
      (node (ref "J100") (pin "A12") (pinfunction "GND_A12") (pintype "power_in"))
      (node (ref "J100") (pin "B1") (pinfunction "GND_B1") (pintype "power_in"))
      (node (ref "J100") (pin "B12") (pinfunction "GND_B12") (pintype "power_in"))
      (node (ref "J101") (pin "5") (pinfunction "5_5") (pintype "passive"))
      (node (ref "J102") (pin "5") (pinfunction "5_5") (pintype "passive"))
      (node (ref "J103") (pin "4") (pinfunction "4_4") (pintype "passive"))
      (node (ref "J104") (pin "4") (pinfunction "4_4") (pintype "passive"))
      (node (ref "J105") (pin "4") (pinfunction "4_4") (pintype "passive"))
      (node (ref "P100") (pin "8") (pinfunction "8_8") (pintype "passive"))
      (node (ref "P101") (pin "2") (pinfunction "2_2") (pintype "passive"))
      (node (ref "R100") (pin "2") (pinfunction "2_2") (pintype "passive"))
      (node (ref "R101") (pin "1") (pinfunction "1_1") (pintype "passive"))
      (node (ref "R104") (pin "1") (pinfunction "1_1") (pintype "passive"))
      (node (ref "R120") (pin "1") (pinfunction "1_1") (pintype "passive"))
      (node (ref "S100") (pin "B1") (pinfunction "CS-C_B1") (pintype "passive"))
      (node (ref "S100") (pin "H3") (pinfunction "H-_H3") (pintype "passive"))
      (node (ref "S100") (pin "S1") (pinfunction "SHIELD_S1") (pintype "passive"))
      (node (ref "S100") (pin "S2") (pinfunction "SHIELD_S2") (pintype "passive"))
      (node (ref "S100") (pin "S3") (pinfunction "SHIELD_S3") (pintype "passive"))
      (node (ref "S100") (pin "S4") (pinfunction "SHIELD_S4") (pintype "passive"))
      (node (ref "S100") (pin "V3") (pinfunction "V-_V3") (pintype "passive"))
      (node (ref "S101") (pin "1") (pinfunction "1_1") (pintype "passive"))
      (node (ref "S101") (pin "2") (pinfunction "2_2") (pintype "passive"))
      (node (ref "SW100") (pin "1") (pinfunction "1_1") (pintype "passive"))
      (node (ref "SW100") (pin "2") (pinfunction "2_2") (pintype "passive"))
      (node (ref "SW100") (pin "4") (pinfunction "4_4") (pintype "passive"))
      (node (ref "SW100") (pin "5") (pinfunction "5_5") (pintype "passive"))
      (node (ref "SW102") (pin "1") (pinfunction "1_1") (pintype "passive"))
      (node (ref "SW102") (pin "2") (pinfunction "2_2") (pintype "passive"))
      (node (ref "SW102") (pin "4") (pinfunction "4_4") (pintype "passive"))
      (node (ref "SW102") (pin "5") (pinfunction "5_5") (pintype "passive"))
      (node (ref "U100") (pin "23") (pinfunction "VSS_1_23") (pintype "power_in"))
      (node (ref "U100") (pin "35") (pinfunction "VSS_2_35") (pintype "power_in"))
      (node (ref "U100") (pin "47") (pinfunction "VSS_3_47") (pintype "power_in"))
      (node (ref "U100") (pin "8") (pinfunction "VSSA_8") (pintype "power_in"))
      (node (ref "U101") (pin "1") (pinfunction "GND_1") (pintype "power_in"))
      (node (ref "U102") (pin "1") (pinfunction "GND_1") (pintype "power_in"))
      (node (ref "U103") (pin "1") (pinfunction "GND_1") (pintype "power_in"))
      (node (ref "Xtal100") (pin "2") (pinfunction "2_2") (pintype "power_in"))
      (node (ref "Xtal100") (pin "4") (pinfunction "4_4") (pintype "power_in"))
    )
    (net (code "34") (name "J_3V3") (class "Default")
      (node (ref "J101") (pin "1") (pinfunction "1_1") (pintype "passive"))
      (node (ref "R110") (pin "2") (pinfunction "2_2") (pintype "passive"))
      (node (ref "R111") (pin "2") (pinfunction "2_2") (pintype "passive"))
      (node (ref "R112") (pin "2") (pinfunction "2_2") (pintype "passive"))
      (node (ref "S100") (pin "H1") (pinfunction "H+_H1") (pintype "passive"))
      (node (ref "S100") (pin "V1") (pinfunction "V+_V1") (pintype "passive"))
    )
    (net (code "35") (name "Net-(C106-Pad2)") (class "Default")
      (node (ref "C106") (pin "2") (pinfunction "2_2") (pintype "passive"))
      (node (ref "J100") (pin "1") (pinfunction "SHIELD_1") (pintype "passive"))
      (node (ref "J100") (pin "2") (pinfunction "SHIELD_2") (pintype "passive"))
      (node (ref "J100") (pin "3") (pinfunction "SHIELD_3") (pintype "passive"))
      (node (ref "J100") (pin "4") (pinfunction "SHIELD_4") (pintype "passive"))
      (node (ref "R104") (pin "2") (pinfunction "2_2") (pintype "passive"))
    )
    (net (code "36") (name "Net-(C111-Pad2)") (class "Default")
      (node (ref "C111") (pin "2") (pinfunction "2_2") (pintype "passive"))
      (node (ref "R108") (pin "1") (pinfunction "1_1") (pintype "passive"))
      (node (ref "R109") (pin "1") (pinfunction "1_1") (pintype "passive"))
      (node (ref "SW100") (pin "3") (pinfunction "3_3") (pintype "passive"))
      (node (ref "SW100") (pin "6") (pinfunction "6_6") (pintype "passive"))
    )
    (net (code "37") (name "Net-(C112-Pad2)") (class "Default")
      (node (ref "C112") (pin "2") (pinfunction "2_2") (pintype "passive"))
      (node (ref "R116") (pin "1") (pinfunction "1_1") (pintype "passive"))
      (node (ref "R117") (pin "1") (pinfunction "1_1") (pintype "passive"))
      (node (ref "SW102") (pin "3") (pinfunction "3_3") (pintype "passive"))
      (node (ref "SW102") (pin "6") (pinfunction "6_6") (pintype "passive"))
    )
    (net (code "38") (name "Net-(C116-Pad2)") (class "Default")
      (node (ref "C116") (pin "2") (pinfunction "2_2") (pintype "passive"))
      (node (ref "R118") (pin "1") (pinfunction "1_1") (pintype "passive"))
      (node (ref "R119") (pin "1") (pinfunction "1_1") (pintype "passive"))
      (node (ref "S101") (pin "3") (pinfunction "3_3") (pintype "passive"))
      (node (ref "S101") (pin "4") (pinfunction "4_4") (pintype "passive"))
    )
    (net (code "39") (name "Net-(D100-A)") (class "Default")
      (node (ref "D100") (pin "2") (pinfunction "A_2") (pintype "passive"))
      (node (ref "D101") (pin "2") (pinfunction "C_2") (pintype "passive"))
      (node (ref "J100") (pin "A4") (pinfunction "VBUS_A4") (pintype "power_in"))
      (node (ref "J100") (pin "A9") (pinfunction "VBUS_A9") (pintype "power_in"))
      (node (ref "J100") (pin "B4") (pinfunction "VBUS_B4") (pintype "power_in"))
      (node (ref "J100") (pin "B9") (pinfunction "VBUS_B9") (pintype "power_in"))
    )
    (net (code "40") (name "Net-(D102-A)") (class "Default")
      (node (ref "D102") (pin "2") (pinfunction "A_2") (pintype "passive"))
      (node (ref "R105") (pin "2") (pinfunction "2_2") (pintype "passive"))
    )
    (net (code "41") (name "Net-(D103-A)") (class "Default")
      (node (ref "D103") (pin "2") (pinfunction "A_2") (pintype "passive"))
      (node (ref "R106") (pin "2") (pinfunction "2_2") (pintype "passive"))
    )
    (net (code "42") (name "Net-(D104-A)") (class "Default")
      (node (ref "D104") (pin "2") (pinfunction "A_2") (pintype "passive"))
      (node (ref "R107") (pin "2") (pinfunction "2_2") (pintype "passive"))
    )
    (net (code "43") (name "Net-(J100-CC1)") (class "Default")
      (node (ref "J100") (pin "A5") (pinfunction "CC1_A5") (pintype "bidirectional"))
      (node (ref "R100") (pin "1") (pinfunction "1_1") (pintype "passive"))
    )
    (net (code "44") (name "Net-(J100-CC2)") (class "Default")
      (node (ref "J100") (pin "B5") (pinfunction "CC2_B5") (pintype "bidirectional"))
      (node (ref "R101") (pin "2") (pinfunction "2_2") (pintype "passive"))
    )
    (net (code "45") (name "Net-(S100-CS-NO)") (class "Default")
      (node (ref "C115") (pin "2") (pinfunction "2_2") (pintype "passive"))
      (node (ref "R112") (pin "1") (pinfunction "1_1") (pintype "passive"))
      (node (ref "R115") (pin "1") (pinfunction "1_1") (pintype "passive"))
      (node (ref "S100") (pin "B2") (pinfunction "CS-NO_B2") (pintype "passive"))
    )
    (net (code "46") (name "Net-(S100-H)") (class "Default")
      (node (ref "C114") (pin "2") (pinfunction "2_2") (pintype "passive"))
      (node (ref "R111") (pin "1") (pinfunction "1_1") (pintype "passive"))
      (node (ref "R114") (pin "1") (pinfunction "1_1") (pintype "passive"))
      (node (ref "S100") (pin "H2") (pinfunction "H_H2") (pintype "passive"))
    )
    (net (code "47") (name "Net-(S100-V)") (class "Default")
      (node (ref "C113") (pin "2") (pinfunction "2_2") (pintype "passive"))
      (node (ref "R110") (pin "1") (pinfunction "1_1") (pintype "passive"))
      (node (ref "R113") (pin "1") (pinfunction "1_1") (pintype "passive"))
      (node (ref "S100") (pin "V2") (pinfunction "V_V2") (pintype "passive"))
    )
    (net (code "48") (name "Net-(U100A-OSC_IN)") (class "Default")
      (node (ref "C117") (pin "2") (pinfunction "2_2") (pintype "passive"))
      (node (ref "U100") (pin "5") (pinfunction "OSC_IN_5") (pintype "bidirectional"))
      (node (ref "Xtal100") (pin "1") (pinfunction "1_1") (pintype "passive"))
    )
    (net (code "49") (name "Net-(U100A-OSC_OUT)") (class "Default")
      (node (ref "C118") (pin "2") (pinfunction "2_2") (pintype "passive"))
      (node (ref "U100") (pin "6") (pinfunction "OSC_OUT_6") (pintype "bidirectional"))
      (node (ref "Xtal100") (pin "3") (pinfunction "3_3") (pintype "passive"))
    )
    (net (code "50") (name "Net-(U101-DATA)") (class "Default")
      (node (ref "R121") (pin "1") (pinfunction "1_1") (pintype "passive"))
      (node (ref "U101") (pin "3") (pinfunction "DATA_3") (pintype "input"))
    )
    (net (code "51") (name "SL_3V3") (class "Default")
      (node (ref "J104") (pin "2") (pinfunction "2_2") (pintype "passive"))
      (node (ref "R108") (pin "2") (pinfunction "2_2") (pintype "passive"))
    )
    (net (code "52") (name "SR_3V3") (class "Default")
      (node (ref "J105") (pin "2") (pinfunction "2_2") (pintype "passive"))
      (node (ref "R116") (pin "2") (pinfunction "2_2") (pintype "passive"))
    )
    (net (code "53") (name "unconnected-(J100-SBU1-PadA8)") (class "Default")
      (node (ref "J100") (pin "A8") (pinfunction "SBU1_A8") (pintype "bidirectional+no_connect"))
    )
    (net (code "54") (name "unconnected-(J100-SBU2-PadB8)") (class "Default")
      (node (ref "J100") (pin "B8") (pinfunction "SBU2_B8") (pintype "bidirectional+no_connect"))
    )
    (net (code "55") (name "unconnected-(J101-Pad3)") (class "Default")
      (node (ref "J101") (pin "3") (pinfunction "3_3") (pintype "passive+no_connect"))
    )
    (net (code "56") (name "unconnected-(J102-Pad3)") (class "Default")
      (node (ref "J102") (pin "3") (pinfunction "3_3") (pintype "passive+no_connect"))
    )
    (net (code "57") (name "unconnected-(J104-Pad3)") (class "Default")
      (node (ref "J104") (pin "3") (pinfunction "3_3") (pintype "passive+no_connect"))
    )
    (net (code "58") (name "unconnected-(J105-Pad1)") (class "Default")
      (node (ref "J105") (pin "1") (pinfunction "1_1") (pintype "passive+no_connect"))
    )
    (net (code "59") (name "unconnected-(U100A-JNTRST-Pad40)") (class "Default")
      (node (ref "U100") (pin "40") (pinfunction "JNTRST_40") (pintype "bidirectional"))
    )
    (net (code "60") (name "unconnected-(U100A-JTDI-Pad38)") (class "Default")
      (node (ref "U100") (pin "38") (pinfunction "JTDI_38") (pintype "bidirectional"))
    )
    (net (code "61") (name "unconnected-(U100A-JTDO-Pad39)") (class "Default")
      (node (ref "U100") (pin "39") (pinfunction "JTDO_39") (pintype "bidirectional"))
    )
    (net (code "62") (name "unconnected-(U100A-PA4-Pad14)") (class "Default")
      (node (ref "U100") (pin "14") (pinfunction "PA4_14") (pintype "bidirectional"))
    )
    (net (code "63") (name "unconnected-(U100A-PA5-Pad15)") (class "Default")
      (node (ref "U100") (pin "15") (pinfunction "PA5_15") (pintype "bidirectional"))
    )
    (net (code "64") (name "unconnected-(U100A-PA6-Pad16)") (class "Default")
      (node (ref "U100") (pin "16") (pinfunction "PA6_16") (pintype "bidirectional"))
    )
    (net (code "65") (name "unconnected-(U100A-PA7-Pad17)") (class "Default")
      (node (ref "U100") (pin "17") (pinfunction "PA7_17") (pintype "bidirectional"))
    )
    (net (code "66") (name "unconnected-(U100A-PA8-Pad29)") (class "Default")
      (node (ref "U100") (pin "29") (pinfunction "PA8_29") (pintype "bidirectional"))
    )
    (net (code "67") (name "unconnected-(U100A-PA9-Pad30)") (class "Default")
      (node (ref "U100") (pin "30") (pinfunction "PA9_30") (pintype "bidirectional"))
    )
    (net (code "68") (name "unconnected-(U100A-PA10-Pad31)") (class "Default")
      (node (ref "U100") (pin "31") (pinfunction "PA10_31") (pintype "bidirectional"))
    )
    (net (code "69") (name "unconnected-(U100A-PB2_{slash}_BOOT1-Pad20)") (class "Default")
      (node (ref "U100") (pin "20") (pinfunction "PB2_/_BOOT1_20") (pintype "bidirectional"))
    )
    (net (code "70") (name "unconnected-(U100A-PB14-Pad27)") (class "Default")
      (node (ref "U100") (pin "27") (pinfunction "PB14_27") (pintype "bidirectional"))
    )
    (net (code "71") (name "unconnected-(U100A-PB15-Pad28)") (class "Default")
      (node (ref "U100") (pin "28") (pinfunction "PB15_28") (pintype "bidirectional"))
    )
    (net (code "72") (name "unconnected-(U100A-PC13-Pad2)") (class "Default")
      (node (ref "U100") (pin "2") (pinfunction "PC13_2") (pintype "bidirectional"))
    )
    (net (code "73") (name "unconnected-(U100A-PC14-Pad3)") (class "Default")
      (node (ref "U100") (pin "3") (pinfunction "PC14_3") (pintype "bidirectional"))
    )
    (net (code "74") (name "unconnected-(U100A-PC15-Pad4)") (class "Default")
      (node (ref "U100") (pin "4") (pinfunction "PC15_4") (pintype "bidirectional"))
    )
  )
)
